# MCB-EMW3166-v2_0_1.net
KiCad netlist of a schematic drawn in EAGLE
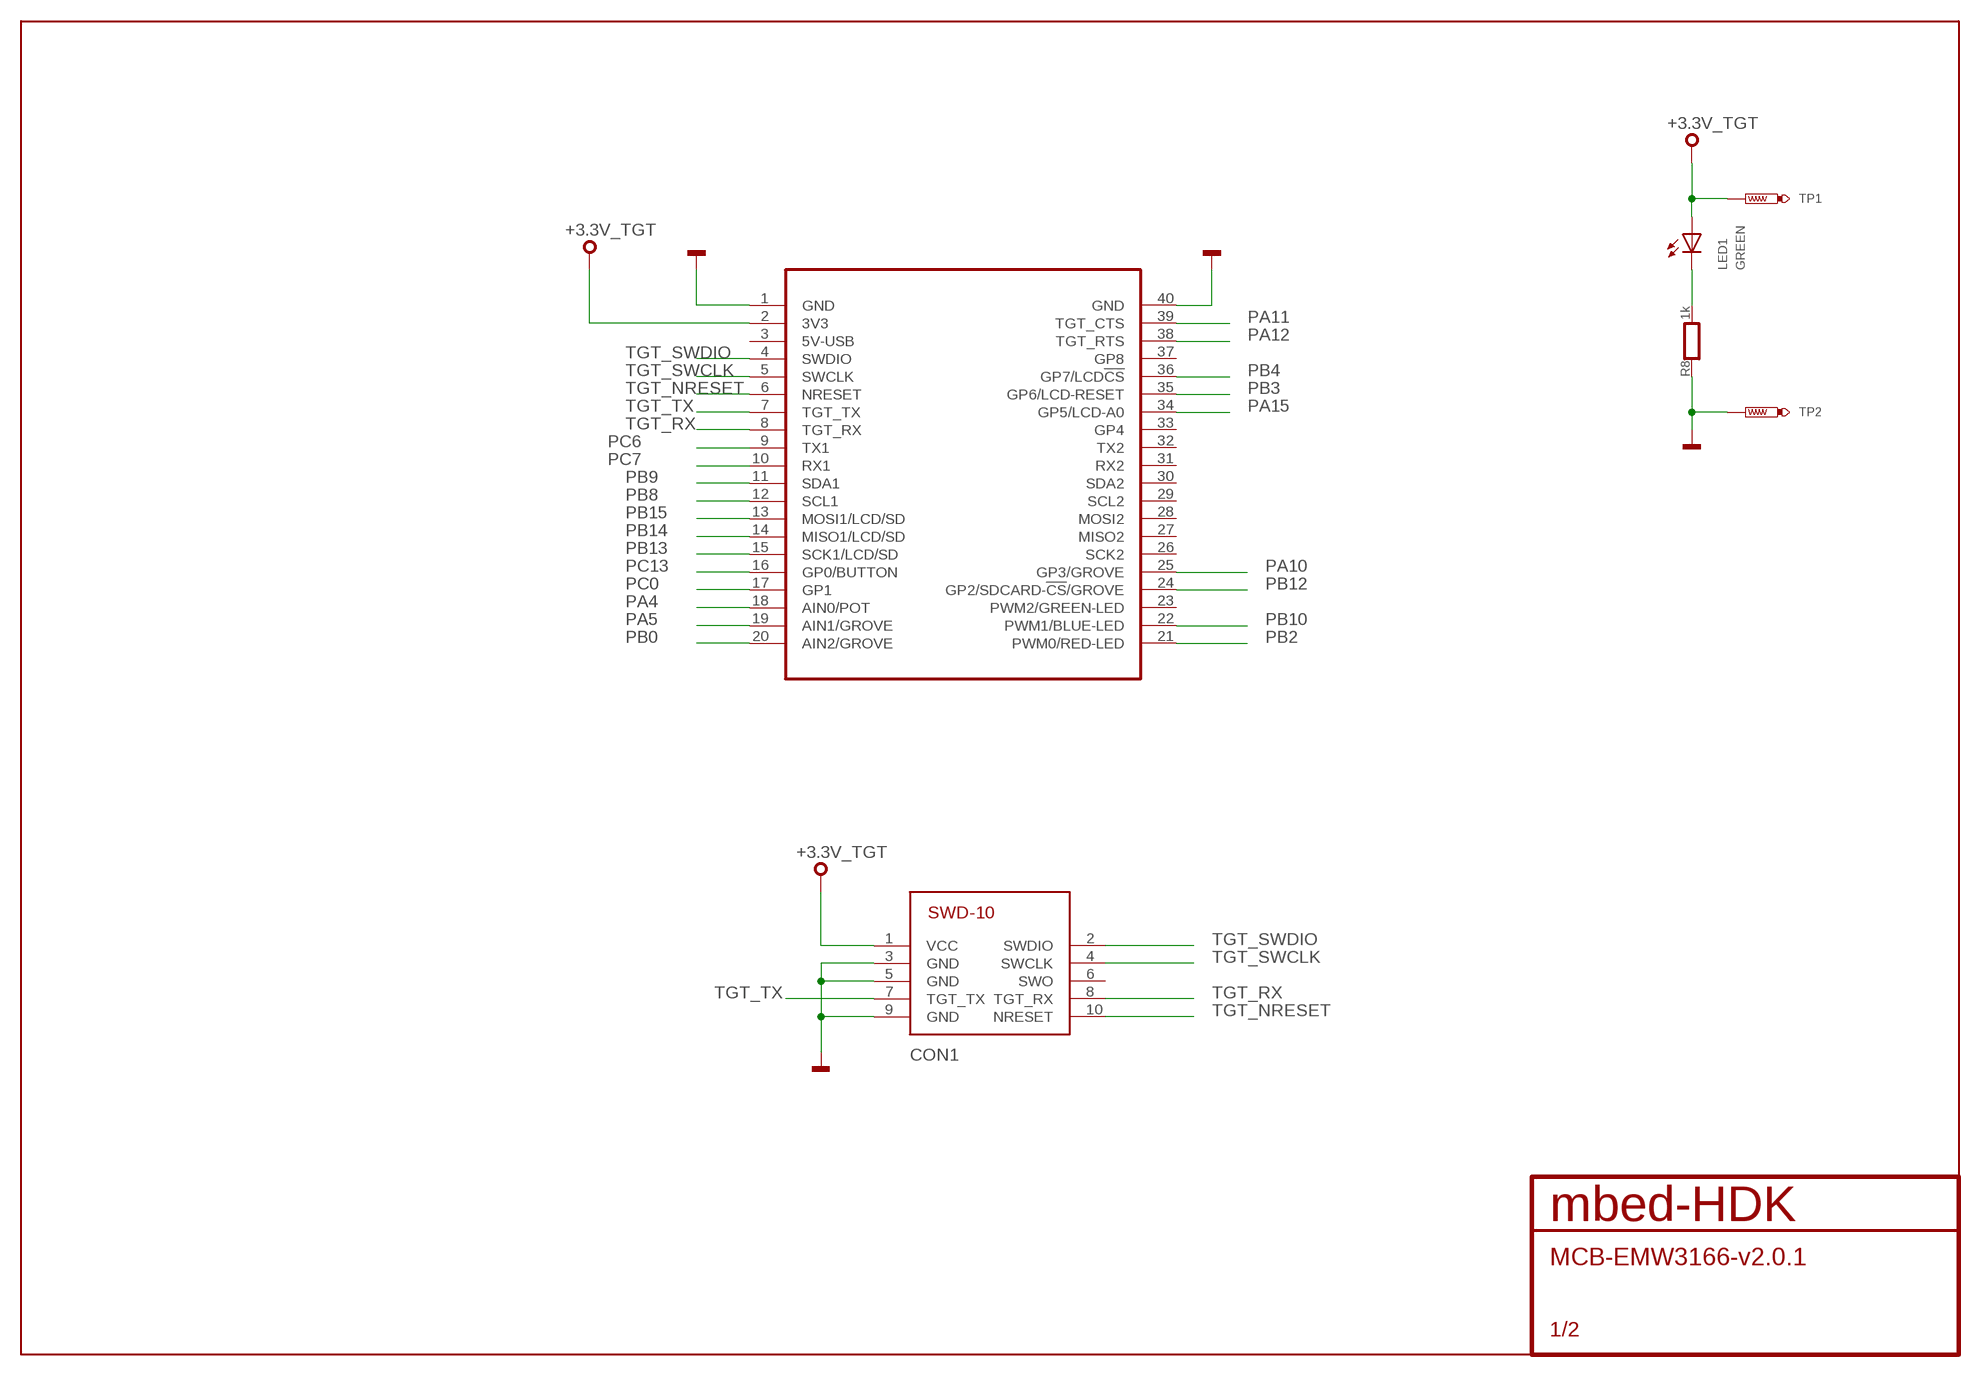
[diagram p0: schematic, sheet 1]
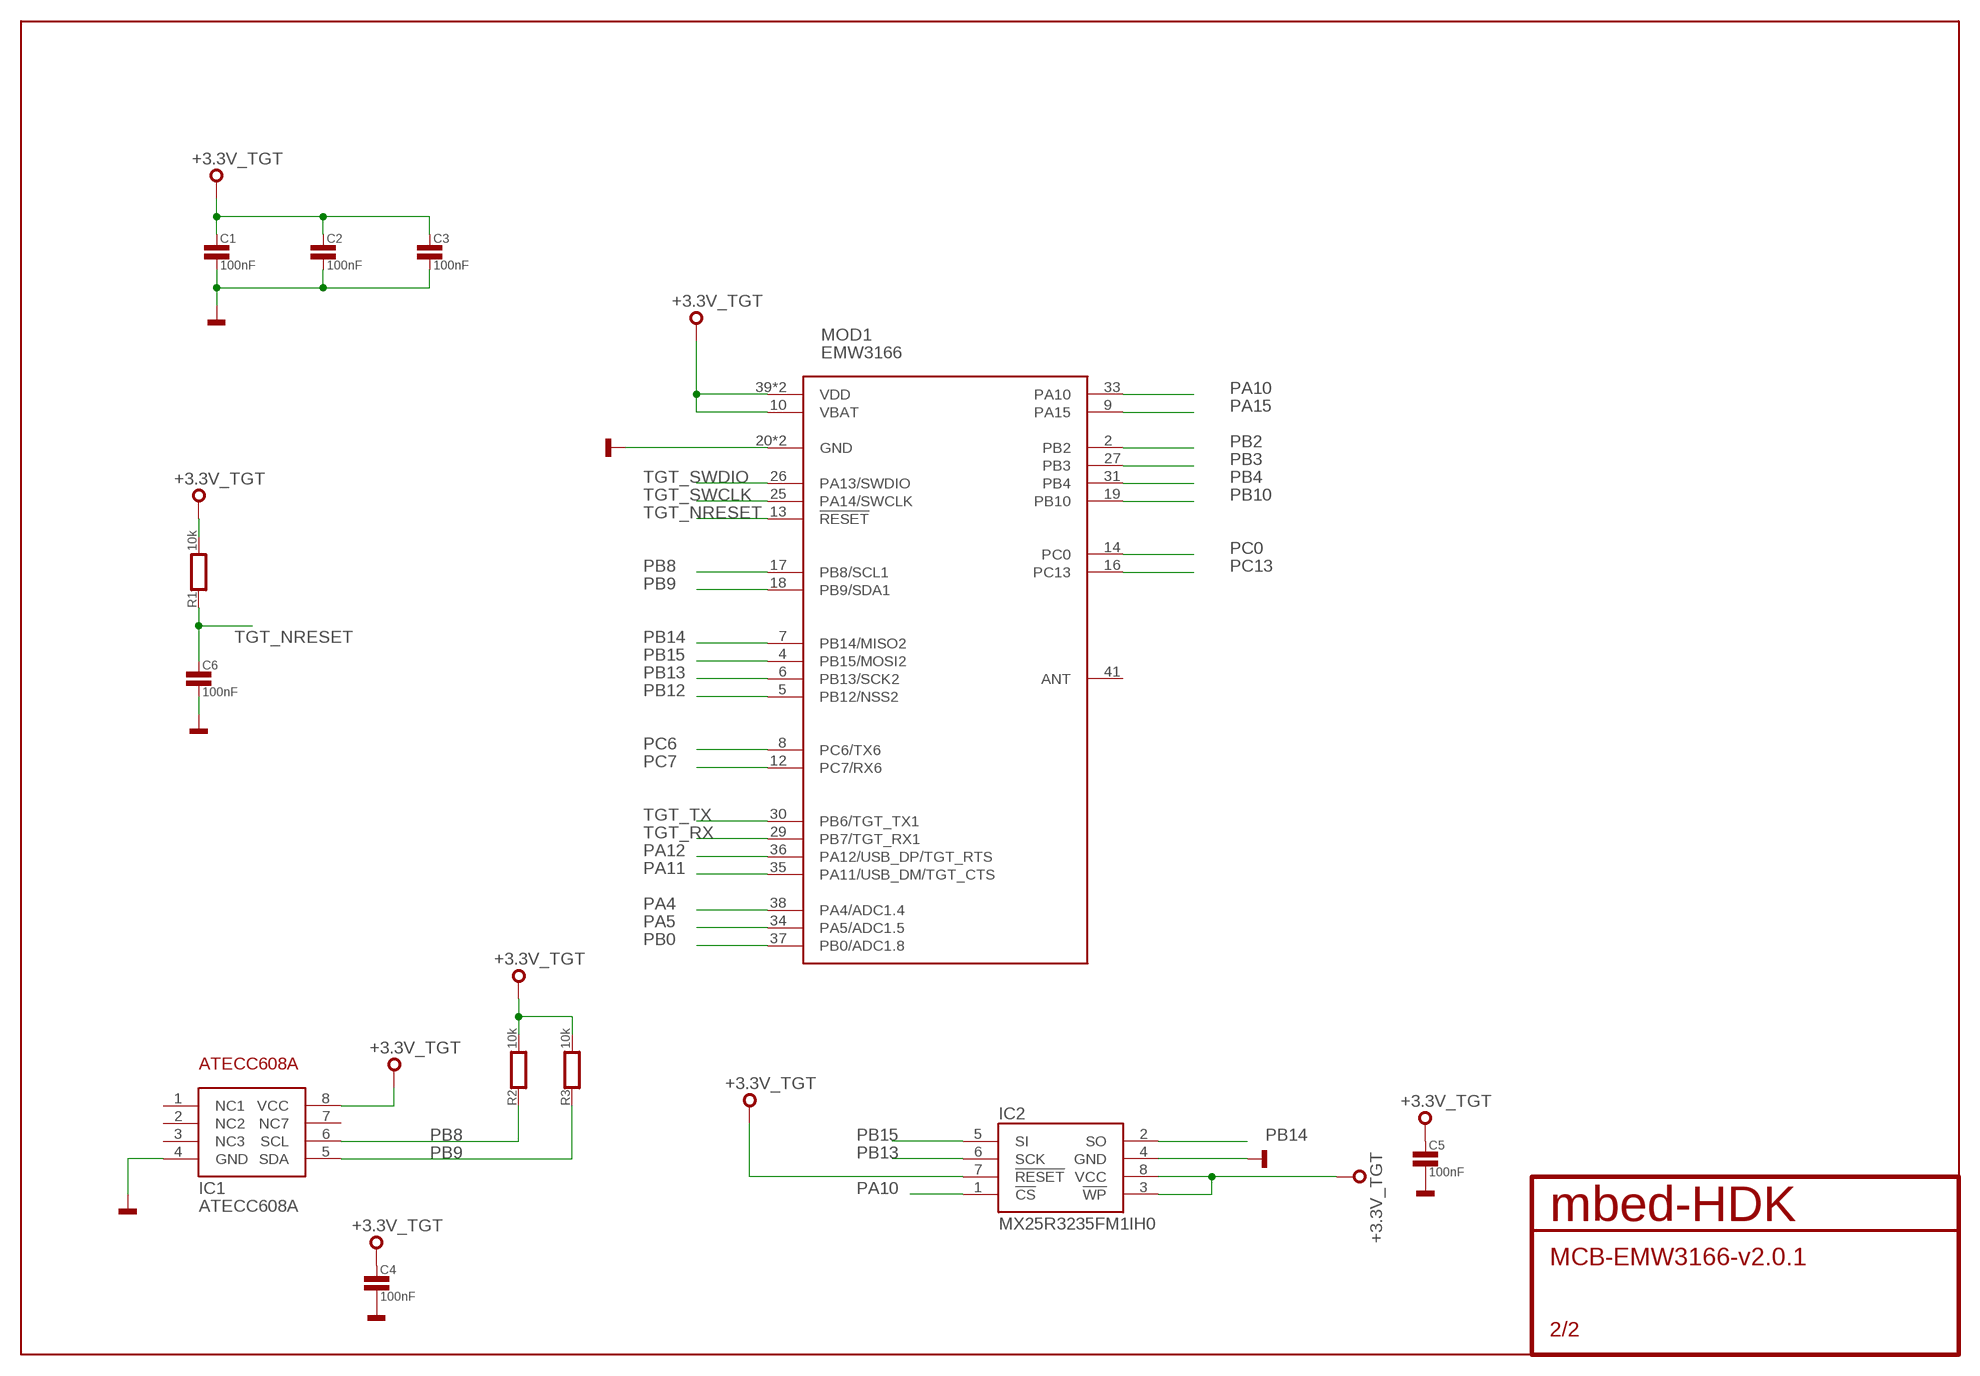
[diagram p1: schematic, sheet 2]

(export (version "E")
  (design (tool "Eeschema 10.0.6"))
  (components
    (comp (ref "CON1")
      (value "SWD-10/TC2050_SMD")
      (footprint "eagle-import:FTSH-105-02")
      (libsource (lib "eagle-import") (part "SWD-10/TC2050_SMD"))
    )
    (comp (ref "LED1")
      (value "GREEN")
      (footprint "eagle-import:CHIPLED_0603")
      (fields (field (name "MF") "Wurth Electronics Inc"))
      (libsource (lib "eagle-import") (part "SMD_LED0603"))
    )
    (comp (ref "MOD2")
      (value "MODULE_DAUGHTER")
      (footprint "eagle-import:MODULE_DAUGHTER")
      (libsource (lib "eagle-import") (part "MODULE_DAUGHTER"))
    )
    (comp (ref "R8")
      (value "1k")
      (footprint "eagle-import:0603")
      (libsource (lib "eagle-import") (part "R0603"))
    )
    (comp (ref "TP1")
      (value "TEST_POINT-50R-PTH")
      (footprint "eagle-import:TP50-PTH")
      (libsource (lib "eagle-import") (part "TEST_POINT-50R-PTH"))
    )
    (comp (ref "TP2")
      (value "TEST_POINT-50R-PTH")
      (footprint "eagle-import:TP50-PTH")
      (libsource (lib "eagle-import") (part "TEST_POINT-50R-PTH"))
    )
    (comp (ref "C1")
      (value "100nF")
      (footprint "eagle-import:0603")
      (libsource (lib "eagle-import") (part "C0603"))
    )
    (comp (ref "C2")
      (value "100nF")
      (footprint "eagle-import:0603")
      (libsource (lib "eagle-import") (part "C0603"))
    )
    (comp (ref "C3")
      (value "100nF")
      (footprint "eagle-import:0603")
      (libsource (lib "eagle-import") (part "C0603"))
    )
    (comp (ref "C4")
      (value "100nF")
      (footprint "eagle-import:0603")
      (libsource (lib "eagle-import") (part "C0603"))
    )
    (comp (ref "C5")
      (value "100nF")
      (footprint "eagle-import:0603")
      (libsource (lib "eagle-import") (part "C0603"))
    )
    (comp (ref "C6")
      (value "100nF")
      (footprint "eagle-import:0603")
      (libsource (lib "eagle-import") (part "C0603"))
    )
    (comp (ref "IC1")
      (value "ATECC608A")
      (footprint "eagle-import:SO8")
      (fields (field (name "MF") "Atmel"))
      (libsource (lib "eagle-import") (part "ATECC608A"))
    )
    (comp (ref "IC2")
      (value "MX25R3235FM1IH0")
      (footprint "eagle-import:SO8")
      (fields (field (name "MF") "Macronix"))
      (libsource (lib "eagle-import") (part "MX25R3235FM1IH0"))
    )
    (comp (ref "MOD1")
      (value "EMW3166")
      (footprint "eagle-import:EMW3166")
      (libsource (lib "eagle-import") (part "EMW3166"))
    )
    (comp (ref "R1")
      (value "10k")
      (footprint "eagle-import:0603")
      (libsource (lib "eagle-import") (part "R0603"))
    )
    (comp (ref "R2")
      (value "10k")
      (footprint "eagle-import:0603")
      (libsource (lib "eagle-import") (part "R0603"))
    )
    (comp (ref "R3")
      (value "10k")
      (footprint "eagle-import:0603")
      (libsource (lib "eagle-import") (part "R0603"))
    )
  )
  (nets
    (net (code "1") (name "+3.3V_TGT") (class "Default")
      (node (ref "C1") (pin "1") (pinfunction "P$1_1") (pintype "passive"))
      (node (ref "C2") (pin "1") (pinfunction "P$1_1") (pintype "passive"))
      (node (ref "C3") (pin "1") (pinfunction "P$1_1") (pintype "passive"))
      (node (ref "C4") (pin "1") (pinfunction "P$1_1") (pintype "passive"))
      (node (ref "C5") (pin "1") (pinfunction "P$1_1") (pintype "passive"))
      (node (ref "CON1") (pin "1") (pinfunction "VCC_1") (pintype "bidirectional"))
      (node (ref "IC1") (pin "8") (pinfunction "VCC_8") (pintype "bidirectional"))
      (node (ref "IC2") (pin "3") (pinfunction "~{WP}_3") (pintype "bidirectional"))
      (node (ref "IC2") (pin "7") (pinfunction "~{RESET}_7") (pintype "bidirectional"))
      (node (ref "IC2") (pin "8") (pinfunction "VCC_8") (pintype "bidirectional"))
      (node (ref "LED1") (pin "A") (pinfunction "A_A") (pintype "passive"))
      (node (ref "MOD1") (pin "10") (pinfunction "VBAT_10") (pintype "bidirectional"))
      (node (ref "MOD1") (pin "39") (pinfunction "VDD_39") (pintype "bidirectional"))
      (node (ref "MOD1") (pin "40") (pinfunction "VDD_40") (pintype "bidirectional"))
      (node (ref "MOD2") (pin "2") (pinfunction "3V3_2") (pintype "bidirectional"))
      (node (ref "R1") (pin "2") (pinfunction "P$2_2") (pintype "passive"))
      (node (ref "R2") (pin "2") (pinfunction "P$2_2") (pintype "passive"))
      (node (ref "R3") (pin "2") (pinfunction "P$2_2") (pintype "passive"))
      (node (ref "TP1") (pin "TP") (pinfunction "TP_TP") (pintype "input"))
    )
    (net (code "2") (name "GND") (class "Default")
      (node (ref "C1") (pin "2") (pinfunction "P$2_2") (pintype "passive"))
      (node (ref "C2") (pin "2") (pinfunction "P$2_2") (pintype "passive"))
      (node (ref "C3") (pin "2") (pinfunction "P$2_2") (pintype "passive"))
      (node (ref "C4") (pin "2") (pinfunction "P$2_2") (pintype "passive"))
      (node (ref "C5") (pin "2") (pinfunction "P$2_2") (pintype "passive"))
      (node (ref "C6") (pin "2") (pinfunction "P$2_2") (pintype "passive"))
      (node (ref "CON1") (pin "3") (pinfunction "GND_3") (pintype "bidirectional"))
      (node (ref "CON1") (pin "5") (pinfunction "GND_5") (pintype "bidirectional"))
      (node (ref "CON1") (pin "9") (pinfunction "GND_9") (pintype "bidirectional"))
      (node (ref "IC1") (pin "4") (pinfunction "GND_4") (pintype "bidirectional"))
      (node (ref "IC2") (pin "4") (pinfunction "GND_4") (pintype "bidirectional"))
      (node (ref "MOD1") (pin "20") (pinfunction "GND_20") (pintype "bidirectional"))
      (node (ref "MOD1") (pin "21") (pinfunction "GND_21") (pintype "bidirectional"))
      (node (ref "MOD2") (pin "1") (pinfunction "GND_1") (pintype "bidirectional"))
      (node (ref "MOD2") (pin "40") (pinfunction "GND_40") (pintype "bidirectional"))
      (node (ref "R8") (pin "1") (pinfunction "P$1_1") (pintype "passive"))
      (node (ref "TP2") (pin "TP") (pinfunction "TP_TP") (pintype "input"))
    )
    (net (code "3") (name "Net-(R8-P$2)") (class "Default")
      (node (ref "LED1") (pin "C") (pinfunction "C_C") (pintype "passive"))
      (node (ref "R8") (pin "2") (pinfunction "P$2_2") (pintype "passive"))
    )
    (net (code "4") (name "PA4") (class "Default")
      (node (ref "MOD1") (pin "38") (pinfunction "PA4/ADC1.4_38") (pintype "bidirectional"))
      (node (ref "MOD2") (pin "18") (pinfunction "AIN0/POT_18") (pintype "bidirectional"))
    )
    (net (code "5") (name "PA5") (class "Default")
      (node (ref "MOD1") (pin "34") (pinfunction "PA5/ADC1.5_34") (pintype "bidirectional"))
      (node (ref "MOD2") (pin "19") (pinfunction "AIN1/GROVE_19") (pintype "bidirectional"))
    )
    (net (code "6") (name "PA10") (class "Default")
      (node (ref "IC2") (pin "1") (pinfunction "~{CS}_1") (pintype "bidirectional"))
      (node (ref "MOD1") (pin "33") (pinfunction "PA10_33") (pintype "bidirectional"))
      (node (ref "MOD2") (pin "25") (pinfunction "GP3/GROVE_25") (pintype "bidirectional"))
    )
    (net (code "7") (name "PA11") (class "Default")
      (node (ref "MOD1") (pin "35") (pinfunction "PA11/USB_DM/TGT_CTS_35") (pintype "bidirectional"))
      (node (ref "MOD2") (pin "39") (pinfunction "TGT_CTS_39") (pintype "bidirectional"))
    )
    (net (code "8") (name "PA12") (class "Default")
      (node (ref "MOD1") (pin "36") (pinfunction "PA12/USB_DP/TGT_RTS_36") (pintype "bidirectional"))
      (node (ref "MOD2") (pin "38") (pinfunction "TGT_RTS_38") (pintype "bidirectional"))
    )
    (net (code "9") (name "PA15") (class "Default")
      (node (ref "MOD1") (pin "9") (pinfunction "PA15_9") (pintype "bidirectional"))
      (node (ref "MOD2") (pin "34") (pinfunction "GP5/LCD-A0_34") (pintype "bidirectional"))
    )
    (net (code "10") (name "PB0") (class "Default")
      (node (ref "MOD1") (pin "37") (pinfunction "PB0/ADC1.8_37") (pintype "bidirectional"))
      (node (ref "MOD2") (pin "20") (pinfunction "AIN2/GROVE_20") (pintype "bidirectional"))
    )
    (net (code "11") (name "PB2") (class "Default")
      (node (ref "MOD1") (pin "2") (pinfunction "PB2_2") (pintype "bidirectional"))
      (node (ref "MOD2") (pin "21") (pinfunction "PWM0/RED-LED_21") (pintype "bidirectional"))
    )
    (net (code "12") (name "PB3") (class "Default")
      (node (ref "MOD1") (pin "27") (pinfunction "PB3_27") (pintype "bidirectional"))
      (node (ref "MOD2") (pin "35") (pinfunction "GP6/LCD-RESET_35") (pintype "bidirectional"))
    )
    (net (code "13") (name "PB4") (class "Default")
      (node (ref "MOD1") (pin "31") (pinfunction "PB4_31") (pintype "bidirectional"))
      (node (ref "MOD2") (pin "36") (pinfunction "GP7/LCD~{CS}_36") (pintype "bidirectional"))
    )
    (net (code "14") (name "PB8") (class "Default")
      (node (ref "IC1") (pin "6") (pinfunction "SCL_6") (pintype "bidirectional"))
      (node (ref "MOD1") (pin "17") (pinfunction "PB8/SCL1_17") (pintype "bidirectional"))
      (node (ref "MOD2") (pin "12") (pinfunction "SCL1_12") (pintype "bidirectional"))
      (node (ref "R2") (pin "1") (pinfunction "P$1_1") (pintype "passive"))
    )
    (net (code "15") (name "PB9") (class "Default")
      (node (ref "IC1") (pin "5") (pinfunction "SDA_5") (pintype "bidirectional"))
      (node (ref "MOD1") (pin "18") (pinfunction "PB9/SDA1_18") (pintype "bidirectional"))
      (node (ref "MOD2") (pin "11") (pinfunction "SDA1_11") (pintype "bidirectional"))
      (node (ref "R3") (pin "1") (pinfunction "P$1_1") (pintype "passive"))
    )
    (net (code "16") (name "PB10") (class "Default")
      (node (ref "MOD1") (pin "19") (pinfunction "PB10_19") (pintype "bidirectional"))
      (node (ref "MOD2") (pin "22") (pinfunction "PWM1/BLUE-LED_22") (pintype "bidirectional"))
    )
    (net (code "17") (name "PB12") (class "Default")
      (node (ref "MOD1") (pin "5") (pinfunction "PB12/NSS2_5") (pintype "bidirectional"))
      (node (ref "MOD2") (pin "24") (pinfunction "GP2/SDCARD-~{CS}/GROVE_24") (pintype "bidirectional"))
    )
    (net (code "18") (name "PB13") (class "Default")
      (node (ref "IC2") (pin "6") (pinfunction "SCK_6") (pintype "bidirectional"))
      (node (ref "MOD1") (pin "6") (pinfunction "PB13/SCK2_6") (pintype "bidirectional"))
      (node (ref "MOD2") (pin "15") (pinfunction "SCK1/LCD/SD_15") (pintype "bidirectional"))
    )
    (net (code "19") (name "PB14") (class "Default")
      (node (ref "IC2") (pin "2") (pinfunction "SO_2") (pintype "bidirectional"))
      (node (ref "MOD1") (pin "7") (pinfunction "PB14/MISO2_7") (pintype "bidirectional"))
      (node (ref "MOD2") (pin "14") (pinfunction "MISO1/LCD/SD_14") (pintype "bidirectional"))
    )
    (net (code "20") (name "PB15") (class "Default")
      (node (ref "IC2") (pin "5") (pinfunction "SI_5") (pintype "bidirectional"))
      (node (ref "MOD1") (pin "4") (pinfunction "PB15/MOSI2_4") (pintype "bidirectional"))
      (node (ref "MOD2") (pin "13") (pinfunction "MOSI1/LCD/SD_13") (pintype "bidirectional"))
    )
    (net (code "21") (name "PC0") (class "Default")
      (node (ref "MOD1") (pin "14") (pinfunction "PC0_14") (pintype "bidirectional"))
      (node (ref "MOD2") (pin "17") (pinfunction "GP1_17") (pintype "bidirectional"))
    )
    (net (code "22") (name "PC6") (class "Default")
      (node (ref "MOD1") (pin "8") (pinfunction "PC6/TX6_8") (pintype "bidirectional"))
      (node (ref "MOD2") (pin "9") (pinfunction "TX1_9") (pintype "bidirectional"))
    )
    (net (code "23") (name "PC7") (class "Default")
      (node (ref "MOD1") (pin "12") (pinfunction "PC7/RX6_12") (pintype "bidirectional"))
      (node (ref "MOD2") (pin "10") (pinfunction "RX1_10") (pintype "bidirectional"))
    )
    (net (code "24") (name "PC13") (class "Default")
      (node (ref "MOD1") (pin "16") (pinfunction "PC13_16") (pintype "bidirectional"))
      (node (ref "MOD2") (pin "16") (pinfunction "GP0/BUTTON_16") (pintype "bidirectional"))
    )
    (net (code "25") (name "TGT_NRESET") (class "Default")
      (node (ref "C6") (pin "1") (pinfunction "P$1_1") (pintype "passive"))
      (node (ref "CON1") (pin "10") (pinfunction "NRESET_10") (pintype "bidirectional"))
      (node (ref "MOD1") (pin "13") (pinfunction "~{RESET}_13") (pintype "bidirectional"))
      (node (ref "MOD2") (pin "6") (pinfunction "NRESET_6") (pintype "bidirectional"))
      (node (ref "R1") (pin "1") (pinfunction "P$1_1") (pintype "passive"))
    )
    (net (code "26") (name "TGT_RX") (class "Default")
      (node (ref "CON1") (pin "8") (pinfunction "TGT_RX_8") (pintype "bidirectional"))
      (node (ref "MOD1") (pin "29") (pinfunction "PB7/TGT_RX1_29") (pintype "bidirectional"))
      (node (ref "MOD2") (pin "8") (pinfunction "TGT_RX_8") (pintype "bidirectional"))
    )
    (net (code "27") (name "TGT_SWCLK") (class "Default")
      (node (ref "CON1") (pin "4") (pinfunction "SWCLK_4") (pintype "bidirectional"))
      (node (ref "MOD1") (pin "25") (pinfunction "PA14/SWCLK_25") (pintype "bidirectional"))
      (node (ref "MOD2") (pin "5") (pinfunction "SWCLK_5") (pintype "bidirectional"))
    )
    (net (code "28") (name "TGT_SWDIO") (class "Default")
      (node (ref "CON1") (pin "2") (pinfunction "SWDIO_2") (pintype "bidirectional"))
      (node (ref "MOD1") (pin "26") (pinfunction "PA13/SWDIO_26") (pintype "bidirectional"))
      (node (ref "MOD2") (pin "4") (pinfunction "SWDIO_4") (pintype "bidirectional"))
    )
    (net (code "29") (name "TGT_TX") (class "Default")
      (node (ref "CON1") (pin "7") (pinfunction "TGT_TX_7") (pintype "bidirectional"))
      (node (ref "MOD1") (pin "30") (pinfunction "PB6/TGT_TX1_30") (pintype "bidirectional"))
      (node (ref "MOD2") (pin "7") (pinfunction "TGT_TX_7") (pintype "bidirectional"))
    )
    (net (code "30") (name "unconnected-(CON1-SWO-Pad6)") (class "Default")
      (node (ref "CON1") (pin "6") (pinfunction "SWO_6") (pintype "bidirectional"))
    )
    (net (code "31") (name "unconnected-(IC1-NC1-Pad1)") (class "Default")
      (node (ref "IC1") (pin "1") (pinfunction "NC1_1") (pintype "bidirectional"))
    )
    (net (code "32") (name "unconnected-(IC1-NC2-Pad2)") (class "Default")
      (node (ref "IC1") (pin "2") (pinfunction "NC2_2") (pintype "bidirectional"))
    )
    (net (code "33") (name "unconnected-(IC1-NC3-Pad3)") (class "Default")
      (node (ref "IC1") (pin "3") (pinfunction "NC3_3") (pintype "bidirectional"))
    )
    (net (code "34") (name "unconnected-(IC1-NC7-Pad7)") (class "Default")
      (node (ref "IC1") (pin "7") (pinfunction "NC7_7") (pintype "bidirectional"))
    )
    (net (code "35") (name "unconnected-(MOD1-ANT-Pad41)") (class "Default")
      (node (ref "MOD1") (pin "41") (pinfunction "ANT_41") (pintype "bidirectional"))
    )
    (net (code "36") (name "unconnected-(MOD2-5V-USB-Pad3)") (class "Default")
      (node (ref "MOD2") (pin "3") (pinfunction "5V-USB_3") (pintype "bidirectional"))
    )
    (net (code "37") (name "unconnected-(MOD2-GP4-Pad33)") (class "Default")
      (node (ref "MOD2") (pin "33") (pinfunction "GP4_33") (pintype "bidirectional"))
    )
    (net (code "38") (name "unconnected-(MOD2-GP8-Pad37)") (class "Default")
      (node (ref "MOD2") (pin "37") (pinfunction "GP8_37") (pintype "bidirectional"))
    )
    (net (code "39") (name "unconnected-(MOD2-MISO2-Pad27)") (class "Default")
      (node (ref "MOD2") (pin "27") (pinfunction "MISO2_27") (pintype "bidirectional"))
    )
    (net (code "40") (name "unconnected-(MOD2-MOSI2-Pad28)") (class "Default")
      (node (ref "MOD2") (pin "28") (pinfunction "MOSI2_28") (pintype "bidirectional"))
    )
    (net (code "41") (name "unconnected-(MOD2-PWM2{slash}GREEN-LED-Pad23)") (class "Default")
      (node (ref "MOD2") (pin "23") (pinfunction "PWM2/GREEN-LED_23") (pintype "bidirectional"))
    )
    (net (code "42") (name "unconnected-(MOD2-RX2-Pad31)") (class "Default")
      (node (ref "MOD2") (pin "31") (pinfunction "RX2_31") (pintype "bidirectional"))
    )
    (net (code "43") (name "unconnected-(MOD2-SCK2-Pad26)") (class "Default")
      (node (ref "MOD2") (pin "26") (pinfunction "SCK2_26") (pintype "bidirectional"))
    )
    (net (code "44") (name "unconnected-(MOD2-SCL2-Pad29)") (class "Default")
      (node (ref "MOD2") (pin "29") (pinfunction "SCL2_29") (pintype "bidirectional"))
    )
    (net (code "45") (name "unconnected-(MOD2-SDA2-Pad30)") (class "Default")
      (node (ref "MOD2") (pin "30") (pinfunction "SDA2_30") (pintype "bidirectional"))
    )
    (net (code "46") (name "unconnected-(MOD2-TX2-Pad32)") (class "Default")
      (node (ref "MOD2") (pin "32") (pinfunction "TX2_32") (pintype "bidirectional"))
    )
  )
)
